# atmegademo2.net
KiCad netlist of a schematic drawn in EAGLE
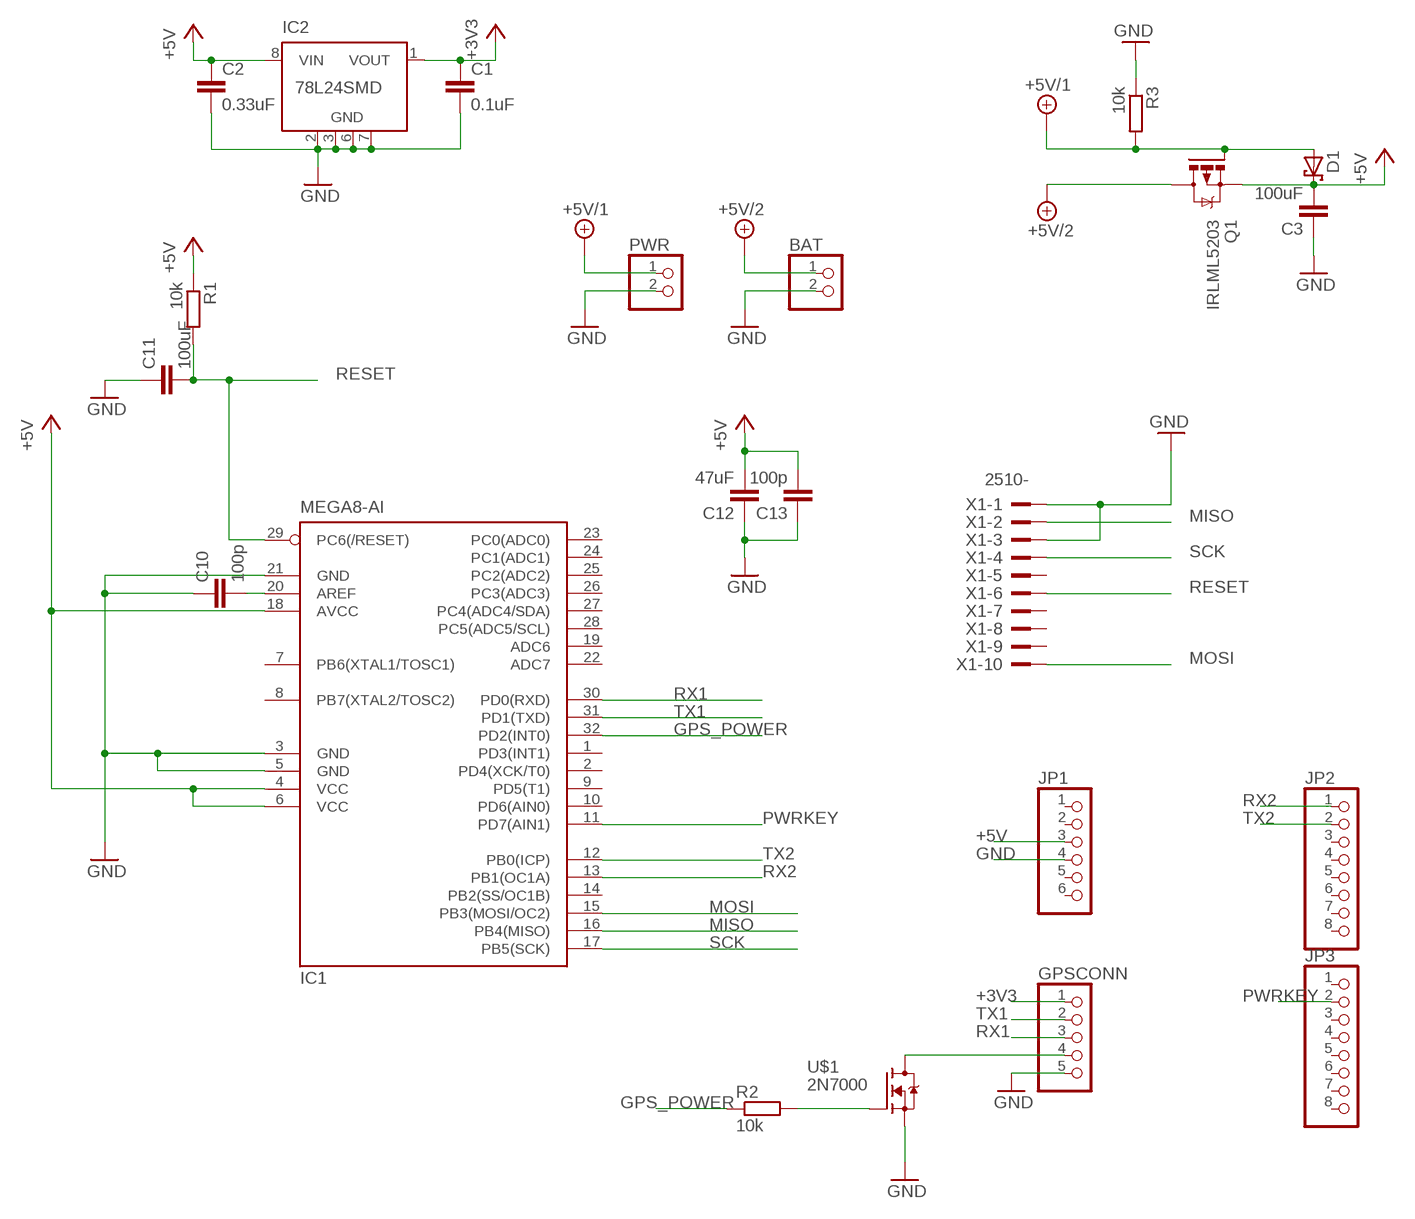
[diagram p0: schematic, sheet 1]

(export (version "E")
  (design (tool "Eeschema 10.0.6"))
  (components
    (comp (ref "BAT")
      (value "PINHD-1X2")
      (footprint "eagle-import:1X02")
      (libsource (lib "eagle-import") (part "PINHD-1X2"))
    )
    (comp (ref "C1")
      (value "0.1uF")
      (footprint "eagle-import:C0805K")
      (libsource (lib "eagle-import") (part "C-EUC0805K"))
    )
    (comp (ref "C2")
      (value "0.33uF")
      (footprint "eagle-import:C0805K")
      (libsource (lib "eagle-import") (part "C-EUC0805K"))
    )
    (comp (ref "C3")
      (value "100uF")
      (footprint "eagle-import:C0805K")
      (libsource (lib "eagle-import") (part "C-EUC0805K"))
    )
    (comp (ref "C10")
      (value "100p")
      (footprint "eagle-import:C0805K")
      (libsource (lib "eagle-import") (part "C-EUC0805K"))
    )
    (comp (ref "C11")
      (value "100uF")
      (footprint "eagle-import:C0805K")
      (libsource (lib "eagle-import") (part "C-EUC0805K"))
    )
    (comp (ref "C12")
      (value "47uF")
      (footprint "eagle-import:C0805K")
      (libsource (lib "eagle-import") (part "C-EUC0805K"))
    )
    (comp (ref "C13")
      (value "100p")
      (footprint "eagle-import:C0805K")
      (libsource (lib "eagle-import") (part "C-EUC0805K"))
    )
    (comp (ref "D1")
      (value "SCHOTTKY-DIODESMD")
      (footprint "eagle-import:SMB")
      (libsource (lib "eagle-import") (part "SCHOTTKY-DIODESMD"))
    )
    (comp (ref "GPSCONN")
      (value "PINHD-1X5")
      (footprint "eagle-import:1X05")
      (libsource (lib "eagle-import") (part "PINHD-1X5"))
    )
    (comp (ref "IC1")
      (value "MEGA8-AI")
      (footprint "eagle-import:TQFP32-08")
      (fields (field (name "MPN") "ATMEGA8-16AU"))
      (libsource (lib "eagle-import") (part "MEGA8-AI"))
    )
    (comp (ref "IC2")
      (value "78L24SMD")
      (footprint "eagle-import:SO08")
      (libsource (lib "eagle-import") (part "78LSMD24"))
    )
    (comp (ref "JP1")
      (value "PINHD-1X6CLEAN")
      (footprint "eagle-import:1X06-CLEAN")
      (libsource (lib "eagle-import") (part "PINHD-1X6CLEAN"))
    )
    (comp (ref "JP2")
      (value "PINHD-1X8CLEANBIG")
      (footprint "eagle-import:1X08-CLEANBIG")
      (libsource (lib "eagle-import") (part "PINHD-1X8CLEANBIG"))
    )
    (comp (ref "JP3")
      (value "PINHD-1X8CLEANBIG")
      (footprint "eagle-import:1X08-CLEANBIG")
      (libsource (lib "eagle-import") (part "PINHD-1X8CLEANBIG"))
    )
    (comp (ref "PWR")
      (value "PINHD-1X2")
      (footprint "eagle-import:1X02")
      (libsource (lib "eagle-import") (part "PINHD-1X2"))
    )
    (comp (ref "Q1")
      (value "IRLML5203")
      (footprint "eagle-import:MICRO3")
      (libsource (lib "eagle-import") (part "IRLML5203"))
    )
    (comp (ref "R1")
      (value "10k")
      (footprint "eagle-import:R0805")
      (libsource (lib "eagle-import") (part "R-EU_R0805"))
    )
    (comp (ref "R2")
      (value "10k")
      (footprint "eagle-import:R0805")
      (libsource (lib "eagle-import") (part "R-EU_R0805"))
    )
    (comp (ref "R3")
      (value "10k")
      (footprint "eagle-import:R0805")
      (libsource (lib "eagle-import") (part "R-EU_R0805"))
    )
    (comp (ref "U$1")
      (value "2N7000")
      (footprint "eagle-import:TO92-")
      (libsource (lib "eagle-import") (part "2N7000"))
    )
    (comp (ref "X1")
      (value "2510-")
      (footprint "eagle-import:PAK100_2500-10")
      (fields (field (name "MF") "3M") (field (name "MPN") "2510-6002UB"))
      (libsource (lib "eagle-import") (part "2510-"))
    )
  )
  (nets
    (net (code "1") (name "+3V3") (class "Default")
      (node (ref "C1") (pin "1") (pinfunction "1_1") (pintype "passive"))
      (node (ref "GPSCONN") (pin "1") (pinfunction "1_1") (pintype "passive"))
      (node (ref "IC2") (pin "1") (pinfunction "VOUT_1") (pintype "output"))
    )
    (net (code "2") (name "+5V") (class "Default")
      (node (ref "C12") (pin "2") (pinfunction "2_2") (pintype "passive"))
      (node (ref "C13") (pin "2") (pinfunction "2_2") (pintype "passive"))
      (node (ref "C2") (pin "1") (pinfunction "1_1") (pintype "passive"))
      (node (ref "C3") (pin "2") (pinfunction "2_2") (pintype "passive"))
      (node (ref "D1") (pin "C") (pinfunction "C_C") (pintype "passive"))
      (node (ref "IC1") (pin "18") (pinfunction "AVCC_18") (pintype "power_in"))
      (node (ref "IC1") (pin "4") (pinfunction "VCC_4") (pintype "power_in"))
      (node (ref "IC1") (pin "6") (pinfunction "VCC_6") (pintype "power_in"))
      (node (ref "IC2") (pin "8") (pinfunction "VIN_8") (pintype "passive"))
      (node (ref "JP1") (pin "3") (pinfunction "3_3") (pintype "passive"))
      (node (ref "Q1") (pin "2") (pinfunction "S_2") (pintype "passive"))
      (node (ref "R1") (pin "1") (pinfunction "1_1") (pintype "passive"))
    )
    (net (code "3") (name "+5V{slash}1") (class "Default")
      (node (ref "D1") (pin "A") (pinfunction "A_A") (pintype "passive"))
      (node (ref "PWR") (pin "1") (pinfunction "1_1") (pintype "passive"))
      (node (ref "Q1") (pin "1") (pinfunction "G_1") (pintype "passive"))
      (node (ref "R3") (pin "2") (pinfunction "2_2") (pintype "passive"))
    )
    (net (code "4") (name "+5V{slash}2") (class "Default")
      (node (ref "BAT") (pin "1") (pinfunction "1_1") (pintype "passive"))
      (node (ref "Q1") (pin "3") (pinfunction "D_3") (pintype "passive"))
    )
    (net (code "5") (name "/GPS_POWER") (class "Default")
      (node (ref "IC1") (pin "32") (pinfunction "PD2(INT0)_32") (pintype "bidirectional"))
      (node (ref "R2") (pin "1") (pinfunction "1_1") (pintype "passive"))
    )
    (net (code "6") (name "/MISO") (class "Default")
      (node (ref "IC1") (pin "16") (pinfunction "PB4(MISO)_16") (pintype "bidirectional"))
      (node (ref "X1") (pin "2") (pinfunction "KL_2") (pintype "passive"))
    )
    (net (code "7") (name "/MOSI") (class "Default")
      (node (ref "IC1") (pin "15") (pinfunction "PB3(MOSI/OC2)_15") (pintype "bidirectional"))
      (node (ref "X1") (pin "10") (pinfunction "KL_10") (pintype "passive"))
    )
    (net (code "8") (name "/PWRKEY") (class "Default")
      (node (ref "IC1") (pin "11") (pinfunction "PD7(AIN1)_11") (pintype "bidirectional"))
      (node (ref "JP3") (pin "2") (pinfunction "2_2") (pintype "passive"))
    )
    (net (code "9") (name "/RESET") (class "Default")
      (node (ref "C11") (pin "2") (pinfunction "2_2") (pintype "passive"))
      (node (ref "IC1") (pin "29") (pinfunction "PC6(/RESET)_29") (pintype "bidirectional"))
      (node (ref "R1") (pin "2") (pinfunction "2_2") (pintype "passive"))
      (node (ref "X1") (pin "6") (pinfunction "KL_6") (pintype "passive"))
    )
    (net (code "10") (name "/RX1") (class "Default")
      (node (ref "GPSCONN") (pin "3") (pinfunction "3_3") (pintype "passive"))
      (node (ref "IC1") (pin "30") (pinfunction "PD0(RXD)_30") (pintype "bidirectional"))
    )
    (net (code "11") (name "/RX2") (class "Default")
      (node (ref "IC1") (pin "13") (pinfunction "PB1(OC1A)_13") (pintype "bidirectional"))
      (node (ref "JP2") (pin "1") (pinfunction "1_1") (pintype "passive"))
    )
    (net (code "12") (name "/SCK") (class "Default")
      (node (ref "IC1") (pin "17") (pinfunction "PB5(SCK)_17") (pintype "bidirectional"))
      (node (ref "X1") (pin "4") (pinfunction "KL_4") (pintype "passive"))
    )
    (net (code "13") (name "/TX1") (class "Default")
      (node (ref "GPSCONN") (pin "2") (pinfunction "2_2") (pintype "passive"))
      (node (ref "IC1") (pin "31") (pinfunction "PD1(TXD)_31") (pintype "bidirectional"))
    )
    (net (code "14") (name "/TX2") (class "Default")
      (node (ref "IC1") (pin "12") (pinfunction "PB0(ICP)_12") (pintype "bidirectional"))
      (node (ref "JP2") (pin "2") (pinfunction "2_2") (pintype "passive"))
    )
    (net (code "15") (name "GND") (class "Default")
      (node (ref "BAT") (pin "2") (pinfunction "2_2") (pintype "passive"))
      (node (ref "C1") (pin "2") (pinfunction "2_2") (pintype "passive"))
      (node (ref "C10") (pin "1") (pinfunction "1_1") (pintype "passive"))
      (node (ref "C11") (pin "1") (pinfunction "1_1") (pintype "passive"))
      (node (ref "C12") (pin "1") (pinfunction "1_1") (pintype "passive"))
      (node (ref "C13") (pin "1") (pinfunction "1_1") (pintype "passive"))
      (node (ref "C2") (pin "2") (pinfunction "2_2") (pintype "passive"))
      (node (ref "C3") (pin "1") (pinfunction "1_1") (pintype "passive"))
      (node (ref "GPSCONN") (pin "5") (pinfunction "5_5") (pintype "passive"))
      (node (ref "IC1") (pin "21") (pinfunction "GND_21") (pintype "power_in"))
      (node (ref "IC1") (pin "3") (pinfunction "GND_3") (pintype "power_in"))
      (node (ref "IC1") (pin "5") (pinfunction "GND_5") (pintype "power_in"))
      (node (ref "IC2") (pin "2") (pinfunction "GND_2") (pintype "power_in"))
      (node (ref "IC2") (pin "3") (pinfunction "GND_3") (pintype "power_in"))
      (node (ref "IC2") (pin "6") (pinfunction "GND_6") (pintype "power_in"))
      (node (ref "IC2") (pin "7") (pinfunction "GND_7") (pintype "power_in"))
      (node (ref "JP1") (pin "4") (pinfunction "4_4") (pintype "passive"))
      (node (ref "PWR") (pin "2") (pinfunction "2_2") (pintype "passive"))
      (node (ref "R3") (pin "1") (pinfunction "1_1") (pintype "passive"))
      (node (ref "U$1") (pin "3") (pinfunction "S_3") (pintype "passive"))
      (node (ref "X1") (pin "1") (pinfunction "KL_1") (pintype "passive"))
      (node (ref "X1") (pin "3") (pinfunction "KL_3") (pintype "passive"))
    )
    (net (code "16") (name "Net-(IC1-AREF)") (class "Default")
      (node (ref "C10") (pin "2") (pinfunction "2_2") (pintype "passive"))
      (node (ref "IC1") (pin "20") (pinfunction "AREF_20") (pintype "passive"))
    )
    (net (code "17") (name "Net-(U$1-D)") (class "Default")
      (node (ref "GPSCONN") (pin "4") (pinfunction "4_4") (pintype "passive"))
      (node (ref "U$1") (pin "1") (pinfunction "D_1") (pintype "passive"))
    )
    (net (code "18") (name "Net-(U$1-G)") (class "Default")
      (node (ref "R2") (pin "2") (pinfunction "2_2") (pintype "passive"))
      (node (ref "U$1") (pin "2") (pinfunction "G_2") (pintype "passive"))
    )
    (net (code "19") (name "unconnected-(IC1-ADC6-Pad19)") (class "Default")
      (node (ref "IC1") (pin "19") (pinfunction "ADC6_19") (pintype "bidirectional"))
    )
    (net (code "20") (name "unconnected-(IC1-ADC7-Pad22)") (class "Default")
      (node (ref "IC1") (pin "22") (pinfunction "ADC7_22") (pintype "bidirectional"))
    )
    (net (code "21") (name "unconnected-(IC1-PB2(SS{slash}OC1B)-Pad14)") (class "Default")
      (node (ref "IC1") (pin "14") (pinfunction "PB2(SS/OC1B)_14") (pintype "bidirectional"))
    )
    (net (code "22") (name "unconnected-(IC1-PB6(XTAL1{slash}TOSC1)-Pad7)") (class "Default")
      (node (ref "IC1") (pin "7") (pinfunction "PB6(XTAL1/TOSC1)_7") (pintype "bidirectional"))
    )
    (net (code "23") (name "unconnected-(IC1-PB7(XTAL2{slash}TOSC2)-Pad8)") (class "Default")
      (node (ref "IC1") (pin "8") (pinfunction "PB7(XTAL2/TOSC2)_8") (pintype "bidirectional"))
    )
    (net (code "24") (name "unconnected-(IC1-PC0(ADC0)-Pad23)") (class "Default")
      (node (ref "IC1") (pin "23") (pinfunction "PC0(ADC0)_23") (pintype "bidirectional"))
    )
    (net (code "25") (name "unconnected-(IC1-PC1(ADC1)-Pad24)") (class "Default")
      (node (ref "IC1") (pin "24") (pinfunction "PC1(ADC1)_24") (pintype "bidirectional"))
    )
    (net (code "26") (name "unconnected-(IC1-PC2(ADC2)-Pad25)") (class "Default")
      (node (ref "IC1") (pin "25") (pinfunction "PC2(ADC2)_25") (pintype "bidirectional"))
    )
    (net (code "27") (name "unconnected-(IC1-PC3(ADC3)-Pad26)") (class "Default")
      (node (ref "IC1") (pin "26") (pinfunction "PC3(ADC3)_26") (pintype "bidirectional"))
    )
    (net (code "28") (name "unconnected-(IC1-PC4(ADC4{slash}SDA)-Pad27)") (class "Default")
      (node (ref "IC1") (pin "27") (pinfunction "PC4(ADC4/SDA)_27") (pintype "bidirectional"))
    )
    (net (code "29") (name "unconnected-(IC1-PC5(ADC5{slash}SCL)-Pad28)") (class "Default")
      (node (ref "IC1") (pin "28") (pinfunction "PC5(ADC5/SCL)_28") (pintype "bidirectional"))
    )
    (net (code "30") (name "unconnected-(IC1-PD3(INT1)-Pad1)") (class "Default")
      (node (ref "IC1") (pin "1") (pinfunction "PD3(INT1)_1") (pintype "bidirectional"))
    )
    (net (code "31") (name "unconnected-(IC1-PD4(XCK{slash}T0)-Pad2)") (class "Default")
      (node (ref "IC1") (pin "2") (pinfunction "PD4(XCK/T0)_2") (pintype "bidirectional"))
    )
    (net (code "32") (name "unconnected-(IC1-PD5(T1)-Pad9)") (class "Default")
      (node (ref "IC1") (pin "9") (pinfunction "PD5(T1)_9") (pintype "bidirectional"))
    )
    (net (code "33") (name "unconnected-(IC1-PD6(AIN0)-Pad10)") (class "Default")
      (node (ref "IC1") (pin "10") (pinfunction "PD6(AIN0)_10") (pintype "bidirectional"))
    )
    (net (code "34") (name "unconnected-(JP1-Pad1)") (class "Default")
      (node (ref "JP1") (pin "1") (pinfunction "1_1") (pintype "passive"))
    )
    (net (code "35") (name "unconnected-(JP1-Pad2)") (class "Default")
      (node (ref "JP1") (pin "2") (pinfunction "2_2") (pintype "passive"))
    )
    (net (code "36") (name "unconnected-(JP1-Pad5)") (class "Default")
      (node (ref "JP1") (pin "5") (pinfunction "5_5") (pintype "passive"))
    )
    (net (code "37") (name "unconnected-(JP1-Pad6)") (class "Default")
      (node (ref "JP1") (pin "6") (pinfunction "6_6") (pintype "passive"))
    )
    (net (code "38") (name "unconnected-(JP2-Pad3)") (class "Default")
      (node (ref "JP2") (pin "3") (pinfunction "3_3") (pintype "passive"))
    )
    (net (code "39") (name "unconnected-(JP2-Pad4)") (class "Default")
      (node (ref "JP2") (pin "4") (pinfunction "4_4") (pintype "passive"))
    )
    (net (code "40") (name "unconnected-(JP2-Pad5)") (class "Default")
      (node (ref "JP2") (pin "5") (pinfunction "5_5") (pintype "passive"))
    )
    (net (code "41") (name "unconnected-(JP2-Pad6)") (class "Default")
      (node (ref "JP2") (pin "6") (pinfunction "6_6") (pintype "passive"))
    )
    (net (code "42") (name "unconnected-(JP2-Pad7)") (class "Default")
      (node (ref "JP2") (pin "7") (pinfunction "7_7") (pintype "passive"))
    )
    (net (code "43") (name "unconnected-(JP2-Pad8)") (class "Default")
      (node (ref "JP2") (pin "8") (pinfunction "8_8") (pintype "passive"))
    )
    (net (code "44") (name "unconnected-(JP3-Pad1)") (class "Default")
      (node (ref "JP3") (pin "1") (pinfunction "1_1") (pintype "passive"))
    )
    (net (code "45") (name "unconnected-(JP3-Pad3)") (class "Default")
      (node (ref "JP3") (pin "3") (pinfunction "3_3") (pintype "passive"))
    )
    (net (code "46") (name "unconnected-(JP3-Pad4)") (class "Default")
      (node (ref "JP3") (pin "4") (pinfunction "4_4") (pintype "passive"))
    )
    (net (code "47") (name "unconnected-(JP3-Pad5)") (class "Default")
      (node (ref "JP3") (pin "5") (pinfunction "5_5") (pintype "passive"))
    )
    (net (code "48") (name "unconnected-(JP3-Pad6)") (class "Default")
      (node (ref "JP3") (pin "6") (pinfunction "6_6") (pintype "passive"))
    )
    (net (code "49") (name "unconnected-(JP3-Pad7)") (class "Default")
      (node (ref "JP3") (pin "7") (pinfunction "7_7") (pintype "passive"))
    )
    (net (code "50") (name "unconnected-(JP3-Pad8)") (class "Default")
      (node (ref "JP3") (pin "8") (pinfunction "8_8") (pintype "passive"))
    )
    (net (code "51") (name "unconnected-(X1F-KL-Pad5)") (class "Default")
      (node (ref "X1") (pin "5") (pinfunction "KL_5") (pintype "passive"))
    )
    (net (code "52") (name "unconnected-(X1H-KL-Pad7)") (class "Default")
      (node (ref "X1") (pin "7") (pinfunction "KL_7") (pintype "passive"))
    )
    (net (code "53") (name "unconnected-(X1I-KL-Pad8)") (class "Default")
      (node (ref "X1") (pin "8") (pinfunction "KL_8") (pintype "passive"))
    )
    (net (code "54") (name "unconnected-(X1J-KL-Pad9)") (class "Default")
      (node (ref "X1") (pin "9") (pinfunction "KL_9") (pintype "passive"))
    )
  )
)
